# Amplifier.net
KiCad netlist of a schematic drawn in EAGLE
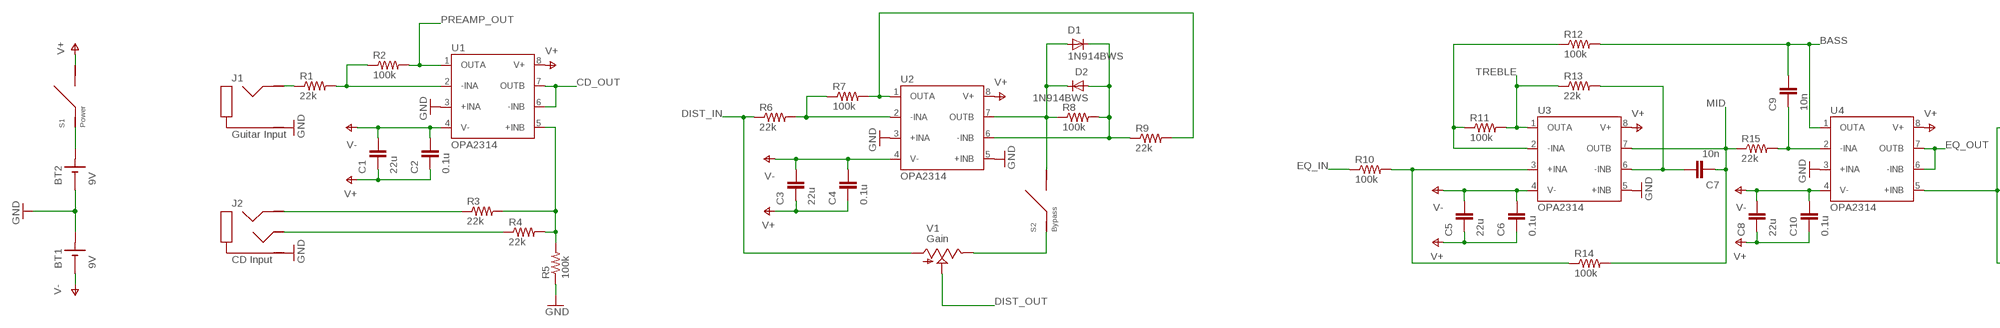
[diagram p0: schematic, sheet 1, part 1 of 2]
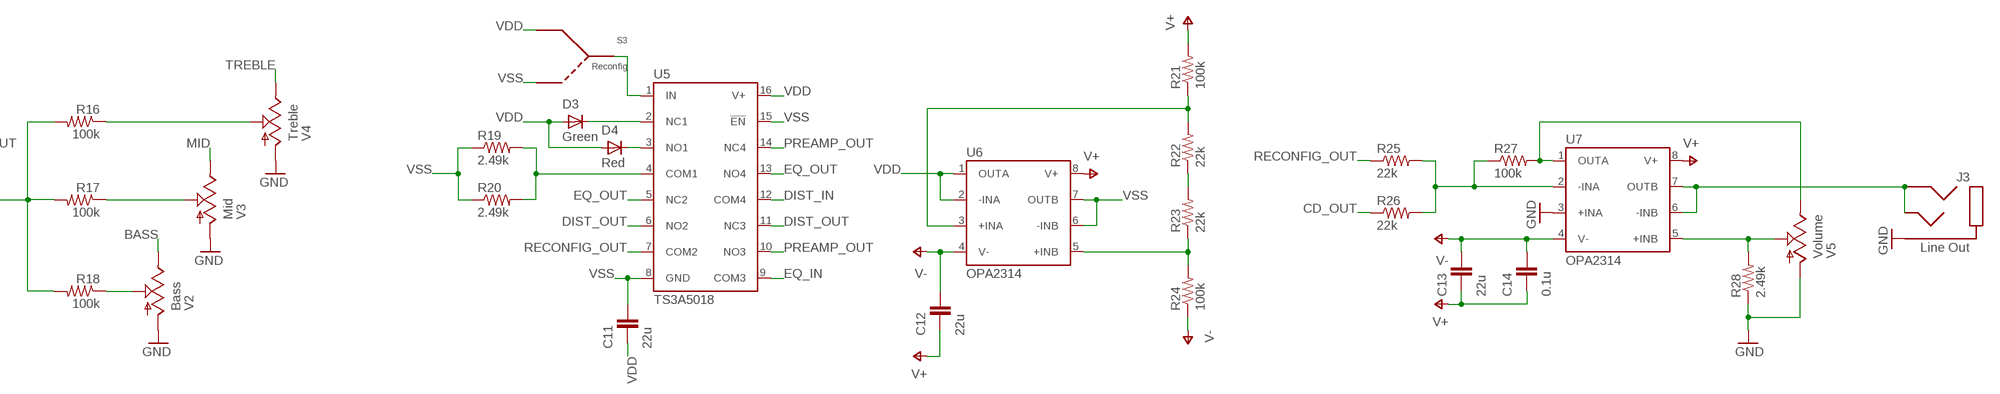
[diagram p1: schematic, sheet 1, part 2 of 2]

(export (version "E")
  (design (tool "Eeschema 10.0.6"))
  (components
    (comp (ref "BT1")
      (value "9V")
      (footprint "eagle-import:9V59X")
      (libsource (lib "eagle-import") (part "9V59X{dblquote}"))
    )
    (comp (ref "BT2")
      (value "9V")
      (footprint "eagle-import:9V59X")
      (libsource (lib "eagle-import") (part "9V59X{dblquote}"))
    )
    (comp (ref "C1")
      (value "22u")
      (footprint "eagle-import:C1206")
      (libsource (lib "eagle-import") (part "C1206"))
    )
    (comp (ref "C2")
      (value "0.1u")
      (footprint "eagle-import:C0402")
      (libsource (lib "eagle-import") (part "C0402"))
    )
    (comp (ref "C3")
      (value "22u")
      (footprint "eagle-import:C1206")
      (libsource (lib "eagle-import") (part "C1206"))
    )
    (comp (ref "C4")
      (value "0.1u")
      (footprint "eagle-import:C0402")
      (libsource (lib "eagle-import") (part "C0402"))
    )
    (comp (ref "C5")
      (value "22u")
      (footprint "eagle-import:C1206")
      (libsource (lib "eagle-import") (part "C1206"))
    )
    (comp (ref "C6")
      (value "0.1u")
      (footprint "eagle-import:C0402")
      (libsource (lib "eagle-import") (part "C0402"))
    )
    (comp (ref "C7")
      (value "10n")
      (footprint "eagle-import:ECW-F6103HL")
      (libsource (lib "eagle-import") (part "CTHRU"))
    )
    (comp (ref "C8")
      (value "22u")
      (footprint "eagle-import:C1206")
      (libsource (lib "eagle-import") (part "C1206"))
    )
    (comp (ref "C9")
      (value "10n")
      (footprint "eagle-import:ECW-F6103HL")
      (libsource (lib "eagle-import") (part "CTHRU"))
    )
    (comp (ref "C10")
      (value "0.1u")
      (footprint "eagle-import:C0402")
      (libsource (lib "eagle-import") (part "C0402"))
    )
    (comp (ref "C11")
      (value "22u")
      (footprint "eagle-import:C1206")
      (libsource (lib "eagle-import") (part "C1206"))
    )
    (comp (ref "C12")
      (value "22u")
      (footprint "eagle-import:C1206")
      (libsource (lib "eagle-import") (part "C1206"))
    )
    (comp (ref "C13")
      (value "22u")
      (footprint "eagle-import:C1206")
      (libsource (lib "eagle-import") (part "C1206"))
    )
    (comp (ref "C14")
      (value "0.1u")
      (footprint "eagle-import:C0402")
      (libsource (lib "eagle-import") (part "C0402"))
    )
    (comp (ref "D1")
      (value "1N914BWS")
      (footprint "eagle-import:SOD-323F")
      (libsource (lib "eagle-import") (part "DSOD-323F"))
    )
    (comp (ref "D2")
      (value "1N914BWS")
      (footprint "eagle-import:SOD-323F")
      (libsource (lib "eagle-import") (part "DSOD-323F"))
    )
    (comp (ref "D3")
      (value "Green")
      (footprint "eagle-import:R0402")
      (libsource (lib "eagle-import") (part "D"))
    )
    (comp (ref "D4")
      (value "Red")
      (footprint "eagle-import:R0402")
      (libsource (lib "eagle-import") (part "D"))
    )
    (comp (ref "J1")
      (value "Guitar Input")
      (footprint "eagle-import:RA49C12B")
      (libsource (lib "eagle-import") (part "RA49C12B"))
    )
    (comp (ref "J2")
      (value "CD Input")
      (footprint "eagle-import:SJ1-3513-SMT-TR")
      (libsource (lib "eagle-import") (part "SJ1-3513-SMT-TR"))
    )
    (comp (ref "J3")
      (value "Line Out")
      (footprint "eagle-import:SJ1-3513-SMT-TR")
      (libsource (lib "eagle-import") (part "SJ1-3513-SMT-TR"))
    )
    (comp (ref "R1")
      (value "22k")
      (footprint "eagle-import:R0402")
      (libsource (lib "eagle-import") (part "R0402"))
    )
    (comp (ref "R2")
      (value "100k")
      (footprint "eagle-import:R0402")
      (libsource (lib "eagle-import") (part "R0402"))
    )
    (comp (ref "R3")
      (value "22k")
      (footprint "eagle-import:R0402")
      (libsource (lib "eagle-import") (part "R0402"))
    )
    (comp (ref "R4")
      (value "22k")
      (footprint "eagle-import:R0402")
      (libsource (lib "eagle-import") (part "R0402"))
    )
    (comp (ref "R5")
      (value "100k")
      (footprint "eagle-import:R0402")
      (libsource (lib "eagle-import") (part "R0402"))
    )
    (comp (ref "R6")
      (value "22k")
      (footprint "eagle-import:R0402")
      (libsource (lib "eagle-import") (part "R0402"))
    )
    (comp (ref "R7")
      (value "100k")
      (footprint "eagle-import:R0402")
      (libsource (lib "eagle-import") (part "R0402"))
    )
    (comp (ref "R8")
      (value "100k")
      (footprint "eagle-import:R0402")
      (libsource (lib "eagle-import") (part "R0402"))
    )
    (comp (ref "R9")
      (value "22k")
      (footprint "eagle-import:R0402")
      (libsource (lib "eagle-import") (part "R0402"))
    )
    (comp (ref "R10")
      (value "100k")
      (footprint "eagle-import:R0402")
      (libsource (lib "eagle-import") (part "R0402"))
    )
    (comp (ref "R11")
      (value "100k")
      (footprint "eagle-import:R0402")
      (libsource (lib "eagle-import") (part "R0402"))
    )
    (comp (ref "R12")
      (value "100k")
      (footprint "eagle-import:R0402")
      (libsource (lib "eagle-import") (part "R0402"))
    )
    (comp (ref "R13")
      (value "22k")
      (footprint "eagle-import:R0402")
      (libsource (lib "eagle-import") (part "R0402"))
    )
    (comp (ref "R14")
      (value "100k")
      (footprint "eagle-import:R0402")
      (libsource (lib "eagle-import") (part "R0402"))
    )
    (comp (ref "R15")
      (value "22k")
      (footprint "eagle-import:R0402")
      (libsource (lib "eagle-import") (part "R0402"))
    )
    (comp (ref "R16")
      (value "100k")
      (footprint "eagle-import:R0402")
      (libsource (lib "eagle-import") (part "R0402"))
    )
    (comp (ref "R17")
      (value "100k")
      (footprint "eagle-import:R0402")
      (libsource (lib "eagle-import") (part "R0402"))
    )
    (comp (ref "R18")
      (value "100k")
      (footprint "eagle-import:R0402")
      (libsource (lib "eagle-import") (part "R0402"))
    )
    (comp (ref "R19")
      (value "2.49k")
      (footprint "eagle-import:R0402")
      (libsource (lib "eagle-import") (part "R0402"))
    )
    (comp (ref "R20")
      (value "2.49k")
      (footprint "eagle-import:R0402")
      (libsource (lib "eagle-import") (part "R0402"))
    )
    (comp (ref "R21")
      (value "100k")
      (footprint "eagle-import:R0402")
      (libsource (lib "eagle-import") (part "R0402"))
    )
    (comp (ref "R22")
      (value "22k")
      (footprint "eagle-import:R0402")
      (libsource (lib "eagle-import") (part "R0402"))
    )
    (comp (ref "R23")
      (value "22k")
      (footprint "eagle-import:R0402")
      (libsource (lib "eagle-import") (part "R0402"))
    )
    (comp (ref "R24")
      (value "100k")
      (footprint "eagle-import:R0402")
      (libsource (lib "eagle-import") (part "R0402"))
    )
    (comp (ref "R25")
      (value "22k")
      (footprint "eagle-import:R0402")
      (libsource (lib "eagle-import") (part "R0402"))
    )
    (comp (ref "R26")
      (value "22k")
      (footprint "eagle-import:R0402")
      (libsource (lib "eagle-import") (part "R0402"))
    )
    (comp (ref "R27")
      (value "100k")
      (footprint "eagle-import:R0402")
      (libsource (lib "eagle-import") (part "R0402"))
    )
    (comp (ref "R28")
      (value "2.49k")
      (footprint "eagle-import:R0402")
      (libsource (lib "eagle-import") (part "R0402"))
    )
    (comp (ref "S1")
      (value "Power")
      (footprint "eagle-import:TMS6T5B2M2RE")
      (libsource (lib "eagle-import") (part "TMS6T5B2M2RE"))
    )
    (comp (ref "S2")
      (value "Bypass")
      (footprint "eagle-import:TMS6T5B2M2RE")
      (libsource (lib "eagle-import") (part "TMS6T5B2M2RE"))
    )
    (comp (ref "S3")
      (value "Reconfig")
      (footprint "eagle-import:TMS1T5B2M2R")
      (libsource (lib "eagle-import") (part "TMS1T5B2M2RE"))
    )
    (comp (ref "U1")
      (value "OPA2314")
      (footprint "eagle-import:8-SOIC")
      (libsource (lib "eagle-import") (part "OPA2314SOIC"))
    )
    (comp (ref "U2")
      (value "OPA2314")
      (footprint "eagle-import:8-SOIC")
      (libsource (lib "eagle-import") (part "OPA2314SOIC"))
    )
    (comp (ref "U3")
      (value "OPA2314")
      (footprint "eagle-import:8-SOIC")
      (libsource (lib "eagle-import") (part "OPA2314SOIC"))
    )
    (comp (ref "U4")
      (value "OPA2314")
      (footprint "eagle-import:8-SOIC")
      (libsource (lib "eagle-import") (part "OPA2314SOIC"))
    )
    (comp (ref "U5")
      (value "TS3A5018")
      (footprint "eagle-import:16-SOIC")
      (libsource (lib "eagle-import") (part "TS3A501816-SOIC"))
    )
    (comp (ref "U6")
      (value "OPA2314")
      (footprint "eagle-import:8-SOIC")
      (libsource (lib "eagle-import") (part "OPA2314SOIC"))
    )
    (comp (ref "U7")
      (value "OPA2314")
      (footprint "eagle-import:8-SOIC")
      (libsource (lib "eagle-import") (part "OPA2314SOIC"))
    )
    (comp (ref "V1")
      (value "Gain")
      (footprint "eagle-import:P0915N-EC15BR10K")
      (libsource (lib "eagle-import") (part "POT"))
    )
    (comp (ref "V2")
      (value "Bass")
      (footprint "eagle-import:P0915N-EC15BR10K")
      (libsource (lib "eagle-import") (part "POT"))
    )
    (comp (ref "V3")
      (value "Mid")
      (footprint "eagle-import:P0915N-EC15BR10K")
      (libsource (lib "eagle-import") (part "POT"))
    )
    (comp (ref "V4")
      (value "Treble")
      (footprint "eagle-import:P0915N-EC15BR10K")
      (libsource (lib "eagle-import") (part "POT"))
    )
    (comp (ref "V5")
      (value "Volume")
      (footprint "eagle-import:P0915N-EC15BR10K")
      (libsource (lib "eagle-import") (part "POT"))
    )
  )
  (nets
    (net (code "1") (name "/BASS") (class "Default")
      (node (ref "C9") (pin "1") (pinfunction "1_1") (pintype "passive"))
      (node (ref "R12") (pin "2") (pinfunction "2_2") (pintype "passive"))
      (node (ref "U4") (pin "1") (pinfunction "OUTA_1") (pintype "output"))
      (node (ref "V2") (pin "3") (pinfunction "E_3") (pintype "passive"))
    )
    (net (code "2") (name "/CD_OUT") (class "Default")
      (node (ref "R26") (pin "1") (pinfunction "1_1") (pintype "passive"))
      (node (ref "U1") (pin "6") (pinfunction "-INB_6") (pintype "input"))
      (node (ref "U1") (pin "7") (pinfunction "OUTB_7") (pintype "output"))
    )
    (net (code "3") (name "/DIST_IN") (class "Default")
      (node (ref "R6") (pin "1") (pinfunction "1_1") (pintype "passive"))
      (node (ref "U5") (pin "12") (pinfunction "COM4_12") (pintype "bidirectional"))
      (node (ref "V1") (pin "1") (pinfunction "A_1") (pintype "passive"))
    )
    (net (code "4") (name "/DIST_OUT") (class "Default")
      (node (ref "U5") (pin "11") (pinfunction "NC3_11") (pintype "bidirectional"))
      (node (ref "U5") (pin "6") (pinfunction "NO2_6") (pintype "bidirectional"))
      (node (ref "V1") (pin "2") (pinfunction "S_2") (pintype "passive"))
    )
    (net (code "5") (name "/EQ_IN") (class "Default")
      (node (ref "R10") (pin "1") (pinfunction "1_1") (pintype "passive"))
      (node (ref "U5") (pin "9") (pinfunction "COM3_9") (pintype "bidirectional"))
    )
    (net (code "6") (name "/EQ_OUT") (class "Default")
      (node (ref "U4") (pin "6") (pinfunction "-INB_6") (pintype "input"))
      (node (ref "U4") (pin "7") (pinfunction "OUTB_7") (pintype "output"))
      (node (ref "U5") (pin "13") (pinfunction "NO4_13") (pintype "bidirectional"))
      (node (ref "U5") (pin "5") (pinfunction "NC2_5") (pintype "bidirectional"))
    )
    (net (code "7") (name "/MID") (class "Default")
      (node (ref "C7") (pin "2") (pinfunction "2_2") (pintype "passive"))
      (node (ref "R14") (pin "2") (pinfunction "2_2") (pintype "passive"))
      (node (ref "R15") (pin "1") (pinfunction "1_1") (pintype "passive"))
      (node (ref "U3") (pin "7") (pinfunction "OUTB_7") (pintype "output"))
      (node (ref "V3") (pin "3") (pinfunction "E_3") (pintype "passive"))
    )
    (net (code "8") (name "/PREAMP_OUT") (class "Default")
      (node (ref "R2") (pin "2") (pinfunction "2_2") (pintype "passive"))
      (node (ref "U1") (pin "1") (pinfunction "OUTA_1") (pintype "output"))
      (node (ref "U5") (pin "10") (pinfunction "NO3_10") (pintype "bidirectional"))
      (node (ref "U5") (pin "14") (pinfunction "NC4_14") (pintype "bidirectional"))
    )
    (net (code "9") (name "/RECONFIG_OUT") (class "Default")
      (node (ref "R25") (pin "1") (pinfunction "1_1") (pintype "passive"))
      (node (ref "U5") (pin "7") (pinfunction "COM2_7") (pintype "bidirectional"))
    )
    (net (code "10") (name "/TREBLE") (class "Default")
      (node (ref "R11") (pin "2") (pinfunction "2_2") (pintype "passive"))
      (node (ref "R13") (pin "1") (pinfunction "1_1") (pintype "passive"))
      (node (ref "U3") (pin "1") (pinfunction "OUTA_1") (pintype "output"))
      (node (ref "V4") (pin "3") (pinfunction "E_3") (pintype "passive"))
    )
    (net (code "11") (name "/VDD") (class "Default")
      (node (ref "C11") (pin "2") (pinfunction "2_2") (pintype "passive"))
      (node (ref "D3") (pin "1") (pinfunction "A_1") (pintype "passive"))
      (node (ref "D4") (pin "1") (pinfunction "A_1") (pintype "passive"))
      (node (ref "S3") (pin "3") (pinfunction "POS1_3") (pintype "passive"))
      (node (ref "U5") (pin "16") (pinfunction "V+_16") (pintype "power_in"))
      (node (ref "U6") (pin "1") (pinfunction "OUTA_1") (pintype "output"))
      (node (ref "U6") (pin "2") (pinfunction "-INA_2") (pintype "input"))
    )
    (net (code "12") (name "/VSS") (class "Default")
      (node (ref "C11") (pin "1") (pinfunction "1_1") (pintype "passive"))
      (node (ref "R19") (pin "1") (pinfunction "1_1") (pintype "passive"))
      (node (ref "R20") (pin "1") (pinfunction "1_1") (pintype "passive"))
      (node (ref "S3") (pin "1") (pinfunction "POS2_1") (pintype "passive"))
      (node (ref "U5") (pin "15") (pinfunction "~{EN}_15") (pintype "input"))
      (node (ref "U5") (pin "8") (pinfunction "GND_8") (pintype "power_in"))
      (node (ref "U6") (pin "6") (pinfunction "-INB_6") (pintype "input"))
      (node (ref "U6") (pin "7") (pinfunction "OUTB_7") (pintype "output"))
    )
    (net (code "13") (name "GND") (class "Default")
      (node (ref "BT1") (pin "4") (pinfunction "+_4") (pintype "passive"))
      (node (ref "BT1") (pin "5") (pinfunction "+_5") (pintype "passive"))
      (node (ref "BT1") (pin "6") (pinfunction "+_6") (pintype "passive"))
      (node (ref "BT2") (pin "1") (pinfunction "-_1") (pintype "passive"))
      (node (ref "BT2") (pin "2") (pinfunction "-_2") (pintype "passive"))
      (node (ref "BT2") (pin "3") (pinfunction "-_3") (pintype "passive"))
      (node (ref "J1") (pin "S1") (pinfunction "COM_S1") (pintype "bidirectional"))
      (node (ref "J1") (pin "S2") (pinfunction "COM_S2") (pintype "bidirectional"))
      (node (ref "J2") (pin "1") (pinfunction "COM_1") (pintype "bidirectional"))
      (node (ref "J3") (pin "1") (pinfunction "COM_1") (pintype "bidirectional"))
      (node (ref "R28") (pin "1") (pinfunction "1_1") (pintype "passive"))
      (node (ref "R5") (pin "1") (pinfunction "1_1") (pintype "passive"))
      (node (ref "U1") (pin "3") (pinfunction "+INA_3") (pintype "input"))
      (node (ref "U2") (pin "3") (pinfunction "+INA_3") (pintype "input"))
      (node (ref "U2") (pin "5") (pinfunction "+INB_5") (pintype "input"))
      (node (ref "U3") (pin "5") (pinfunction "+INB_5") (pintype "input"))
      (node (ref "U4") (pin "3") (pinfunction "+INA_3") (pintype "input"))
      (node (ref "U7") (pin "3") (pinfunction "+INA_3") (pintype "input"))
      (node (ref "V2") (pin "1") (pinfunction "A_1") (pintype "passive"))
      (node (ref "V3") (pin "1") (pinfunction "A_1") (pintype "passive"))
      (node (ref "V4") (pin "1") (pinfunction "A_1") (pintype "passive"))
      (node (ref "V5") (pin "1") (pinfunction "A_1") (pintype "passive"))
    )
    (net (code "14") (name "Net-(D1-A)") (class "Default")
      (node (ref "D1") (pin "2") (pinfunction "A_2") (pintype "passive"))
      (node (ref "D2") (pin "1") (pinfunction "C_1") (pintype "passive"))
      (node (ref "R8") (pin "1") (pinfunction "1_1") (pintype "passive"))
      (node (ref "S2") (pin "1") (pinfunction "P$2_1") (pintype "passive"))
      (node (ref "U2") (pin "7") (pinfunction "OUTB_7") (pintype "output"))
    )
    (net (code "15") (name "Net-(D1-C)") (class "Default")
      (node (ref "D1") (pin "1") (pinfunction "C_1") (pintype "passive"))
      (node (ref "D2") (pin "2") (pinfunction "A_2") (pintype "passive"))
      (node (ref "R8") (pin "2") (pinfunction "2_2") (pintype "passive"))
      (node (ref "R9") (pin "1") (pinfunction "1_1") (pintype "passive"))
      (node (ref "U2") (pin "6") (pinfunction "-INB_6") (pintype "input"))
    )
    (net (code "16") (name "Net-(D3-C)") (class "Default")
      (node (ref "D3") (pin "2") (pinfunction "C_2") (pintype "passive"))
      (node (ref "U5") (pin "2") (pinfunction "NC1_2") (pintype "bidirectional"))
    )
    (net (code "17") (name "Net-(D4-C)") (class "Default")
      (node (ref "D4") (pin "2") (pinfunction "C_2") (pintype "passive"))
      (node (ref "U5") (pin "3") (pinfunction "NO1_3") (pintype "bidirectional"))
    )
    (net (code "18") (name "Net-(J1-SIG)") (class "Default")
      (node (ref "J1") (pin "T") (pinfunction "SIG_T") (pintype "bidirectional"))
      (node (ref "R1") (pin "1") (pinfunction "1_1") (pintype "passive"))
    )
    (net (code "19") (name "Net-(J2-LEFT)") (class "Default")
      (node (ref "J2") (pin "2") (pinfunction "LEFT_2") (pintype "bidirectional"))
      (node (ref "R4") (pin "1") (pinfunction "1_1") (pintype "passive"))
    )
    (net (code "20") (name "Net-(J2-RIGHT)") (class "Default")
      (node (ref "J2") (pin "3") (pinfunction "RIGHT_3") (pintype "bidirectional"))
      (node (ref "R3") (pin "1") (pinfunction "1_1") (pintype "passive"))
    )
    (net (code "21") (name "Net-(J3-LEFT)") (class "Default")
      (node (ref "J3") (pin "2") (pinfunction "LEFT_2") (pintype "bidirectional"))
      (node (ref "J3") (pin "3") (pinfunction "RIGHT_3") (pintype "bidirectional"))
      (node (ref "U7") (pin "6") (pinfunction "-INB_6") (pintype "input"))
      (node (ref "U7") (pin "7") (pinfunction "OUTB_7") (pintype "output"))
    )
    (net (code "22") (name "Net-(R22-Pad1)") (class "Default")
      (node (ref "R22") (pin "1") (pinfunction "1_1") (pintype "passive"))
      (node (ref "R23") (pin "2") (pinfunction "2_2") (pintype "passive"))
    )
    (net (code "23") (name "Net-(S1-P$1)") (class "Default")
      (node (ref "BT2") (pin "4") (pinfunction "+_4") (pintype "passive"))
      (node (ref "BT2") (pin "5") (pinfunction "+_5") (pintype "passive"))
      (node (ref "BT2") (pin "6") (pinfunction "+_6") (pintype "passive"))
      (node (ref "S1") (pin "3") (pinfunction "P$1_3") (pintype "passive"))
    )
    (net (code "24") (name "Net-(S2-P$1)") (class "Default")
      (node (ref "S2") (pin "3") (pinfunction "P$1_3") (pintype "passive"))
      (node (ref "V1") (pin "3") (pinfunction "E_3") (pintype "passive"))
    )
    (net (code "25") (name "Net-(S3-COM)") (class "Default")
      (node (ref "S3") (pin "2") (pinfunction "COM_2") (pintype "passive"))
      (node (ref "U5") (pin "1") (pinfunction "IN_1") (pintype "input"))
    )
    (net (code "26") (name "Net-(U1-+INB)") (class "Default")
      (node (ref "R3") (pin "2") (pinfunction "2_2") (pintype "passive"))
      (node (ref "R4") (pin "2") (pinfunction "2_2") (pintype "passive"))
      (node (ref "R5") (pin "2") (pinfunction "2_2") (pintype "passive"))
      (node (ref "U1") (pin "5") (pinfunction "+INB_5") (pintype "input"))
    )
    (net (code "27") (name "Net-(U1--INA)") (class "Default")
      (node (ref "R1") (pin "2") (pinfunction "2_2") (pintype "passive"))
      (node (ref "R2") (pin "1") (pinfunction "1_1") (pintype "passive"))
      (node (ref "U1") (pin "2") (pinfunction "-INA_2") (pintype "input"))
    )
    (net (code "28") (name "Net-(U2--INA)") (class "Default")
      (node (ref "R6") (pin "2") (pinfunction "2_2") (pintype "passive"))
      (node (ref "R7") (pin "1") (pinfunction "1_1") (pintype "passive"))
      (node (ref "U2") (pin "2") (pinfunction "-INA_2") (pintype "input"))
    )
    (net (code "29") (name "Net-(U2-OUTA)") (class "Default")
      (node (ref "R7") (pin "2") (pinfunction "2_2") (pintype "passive"))
      (node (ref "R9") (pin "2") (pinfunction "2_2") (pintype "passive"))
      (node (ref "U2") (pin "1") (pinfunction "OUTA_1") (pintype "output"))
    )
    (net (code "30") (name "Net-(U3-+INA)") (class "Default")
      (node (ref "R10") (pin "2") (pinfunction "2_2") (pintype "passive"))
      (node (ref "R14") (pin "1") (pinfunction "1_1") (pintype "passive"))
      (node (ref "U3") (pin "3") (pinfunction "+INA_3") (pintype "input"))
    )
    (net (code "31") (name "Net-(U3--INA)") (class "Default")
      (node (ref "R11") (pin "1") (pinfunction "1_1") (pintype "passive"))
      (node (ref "R12") (pin "1") (pinfunction "1_1") (pintype "passive"))
      (node (ref "U3") (pin "2") (pinfunction "-INA_2") (pintype "input"))
    )
    (net (code "32") (name "Net-(U3--INB)") (class "Default")
      (node (ref "C7") (pin "1") (pinfunction "1_1") (pintype "passive"))
      (node (ref "R13") (pin "2") (pinfunction "2_2") (pintype "passive"))
      (node (ref "U3") (pin "6") (pinfunction "-INB_6") (pintype "input"))
    )
    (net (code "33") (name "Net-(U4-+INB)") (class "Default")
      (node (ref "R16") (pin "2") (pinfunction "2_2") (pintype "passive"))
      (node (ref "R17") (pin "2") (pinfunction "2_2") (pintype "passive"))
      (node (ref "R18") (pin "2") (pinfunction "2_2") (pintype "passive"))
      (node (ref "U4") (pin "5") (pinfunction "+INB_5") (pintype "input"))
    )
    (net (code "34") (name "Net-(U4--INA)") (class "Default")
      (node (ref "C9") (pin "2") (pinfunction "2_2") (pintype "passive"))
      (node (ref "R15") (pin "2") (pinfunction "2_2") (pintype "passive"))
      (node (ref "U4") (pin "2") (pinfunction "-INA_2") (pintype "input"))
    )
    (net (code "35") (name "Net-(U5-COM1)") (class "Default")
      (node (ref "R19") (pin "2") (pinfunction "2_2") (pintype "passive"))
      (node (ref "R20") (pin "2") (pinfunction "2_2") (pintype "passive"))
      (node (ref "U5") (pin "4") (pinfunction "COM1_4") (pintype "bidirectional"))
    )
    (net (code "36") (name "Net-(U6-+INA)") (class "Default")
      (node (ref "R21") (pin "1") (pinfunction "1_1") (pintype "passive"))
      (node (ref "R22") (pin "2") (pinfunction "2_2") (pintype "passive"))
      (node (ref "U6") (pin "3") (pinfunction "+INA_3") (pintype "input"))
    )
    (net (code "37") (name "Net-(U6-+INB)") (class "Default")
      (node (ref "R23") (pin "1") (pinfunction "1_1") (pintype "passive"))
      (node (ref "R24") (pin "2") (pinfunction "2_2") (pintype "passive"))
      (node (ref "U6") (pin "5") (pinfunction "+INB_5") (pintype "input"))
    )
    (net (code "38") (name "Net-(U7-+INB)") (class "Default")
      (node (ref "R28") (pin "2") (pinfunction "2_2") (pintype "passive"))
      (node (ref "U7") (pin "5") (pinfunction "+INB_5") (pintype "input"))
      (node (ref "V5") (pin "2") (pinfunction "S_2") (pintype "passive"))
    )
    (net (code "39") (name "Net-(U7--INA)") (class "Default")
      (node (ref "R25") (pin "2") (pinfunction "2_2") (pintype "passive"))
      (node (ref "R26") (pin "2") (pinfunction "2_2") (pintype "passive"))
      (node (ref "R27") (pin "1") (pinfunction "1_1") (pintype "passive"))
      (node (ref "U7") (pin "2") (pinfunction "-INA_2") (pintype "input"))
    )
    (net (code "40") (name "Net-(U7-OUTA)") (class "Default")
      (node (ref "R27") (pin "2") (pinfunction "2_2") (pintype "passive"))
      (node (ref "U7") (pin "1") (pinfunction "OUTA_1") (pintype "output"))
      (node (ref "V5") (pin "3") (pinfunction "E_3") (pintype "passive"))
    )
    (net (code "41") (name "Net-(V2-S)") (class "Default")
      (node (ref "R18") (pin "1") (pinfunction "1_1") (pintype "passive"))
      (node (ref "V2") (pin "2") (pinfunction "S_2") (pintype "passive"))
    )
    (net (code "42") (name "Net-(V3-S)") (class "Default")
      (node (ref "R17") (pin "1") (pinfunction "1_1") (pintype "passive"))
      (node (ref "V3") (pin "2") (pinfunction "S_2") (pintype "passive"))
    )
    (net (code "43") (name "Net-(V4-S)") (class "Default")
      (node (ref "R16") (pin "1") (pinfunction "1_1") (pintype "passive"))
      (node (ref "V4") (pin "2") (pinfunction "S_2") (pintype "passive"))
    )
    (net (code "44") (name "V+") (class "Default")
      (node (ref "C1") (pin "2") (pinfunction "2_2") (pintype "passive"))
      (node (ref "C10") (pin "2") (pinfunction "2_2") (pintype "passive"))
      (node (ref "C12") (pin "2") (pinfunction "2_2") (pintype "passive"))
      (node (ref "C13") (pin "2") (pinfunction "2_2") (pintype "passive"))
      (node (ref "C14") (pin "2") (pinfunction "2_2") (pintype "passive"))
      (node (ref "C2") (pin "2") (pinfunction "2_2") (pintype "passive"))
      (node (ref "C3") (pin "2") (pinfunction "2_2") (pintype "passive"))
      (node (ref "C4") (pin "2") (pinfunction "2_2") (pintype "passive"))
      (node (ref "C5") (pin "2") (pinfunction "2_2") (pintype "passive"))
      (node (ref "C6") (pin "2") (pinfunction "2_2") (pintype "passive"))
      (node (ref "C8") (pin "2") (pinfunction "2_2") (pintype "passive"))
      (node (ref "R21") (pin "2") (pinfunction "2_2") (pintype "passive"))
      (node (ref "S1") (pin "1") (pinfunction "P$2_1") (pintype "passive"))
      (node (ref "U1") (pin "8") (pinfunction "V+_8") (pintype "power_in"))
      (node (ref "U2") (pin "8") (pinfunction "V+_8") (pintype "power_in"))
      (node (ref "U3") (pin "8") (pinfunction "V+_8") (pintype "power_in"))
      (node (ref "U4") (pin "8") (pinfunction "V+_8") (pintype "power_in"))
      (node (ref "U6") (pin "8") (pinfunction "V+_8") (pintype "power_in"))
      (node (ref "U7") (pin "8") (pinfunction "V+_8") (pintype "power_in"))
    )
    (net (code "45") (name "V-") (class "Default")
      (node (ref "BT1") (pin "1") (pinfunction "-_1") (pintype "passive"))
      (node (ref "BT1") (pin "2") (pinfunction "-_2") (pintype "passive"))
      (node (ref "BT1") (pin "3") (pinfunction "-_3") (pintype "passive"))
      (node (ref "C1") (pin "1") (pinfunction "1_1") (pintype "passive"))
      (node (ref "C10") (pin "1") (pinfunction "1_1") (pintype "passive"))
      (node (ref "C12") (pin "1") (pinfunction "1_1") (pintype "passive"))
      (node (ref "C13") (pin "1") (pinfunction "1_1") (pintype "passive"))
      (node (ref "C14") (pin "1") (pinfunction "1_1") (pintype "passive"))
      (node (ref "C2") (pin "1") (pinfunction "1_1") (pintype "passive"))
      (node (ref "C3") (pin "1") (pinfunction "1_1") (pintype "passive"))
      (node (ref "C4") (pin "1") (pinfunction "1_1") (pintype "passive"))
      (node (ref "C5") (pin "1") (pinfunction "1_1") (pintype "passive"))
      (node (ref "C6") (pin "1") (pinfunction "1_1") (pintype "passive"))
      (node (ref "C8") (pin "1") (pinfunction "1_1") (pintype "passive"))
      (node (ref "R24") (pin "1") (pinfunction "1_1") (pintype "passive"))
      (node (ref "U1") (pin "4") (pinfunction "V-_4") (pintype "power_in"))
      (node (ref "U2") (pin "4") (pinfunction "V-_4") (pintype "power_in"))
      (node (ref "U3") (pin "4") (pinfunction "V-_4") (pintype "power_in"))
      (node (ref "U4") (pin "4") (pinfunction "V-_4") (pintype "power_in"))
      (node (ref "U6") (pin "4") (pinfunction "V-_4") (pintype "power_in"))
      (node (ref "U7") (pin "4") (pinfunction "V-_4") (pintype "power_in"))
    )
  )
)
